# Microcontroller.net
KiCad netlist of a schematic drawn in Altium Designer
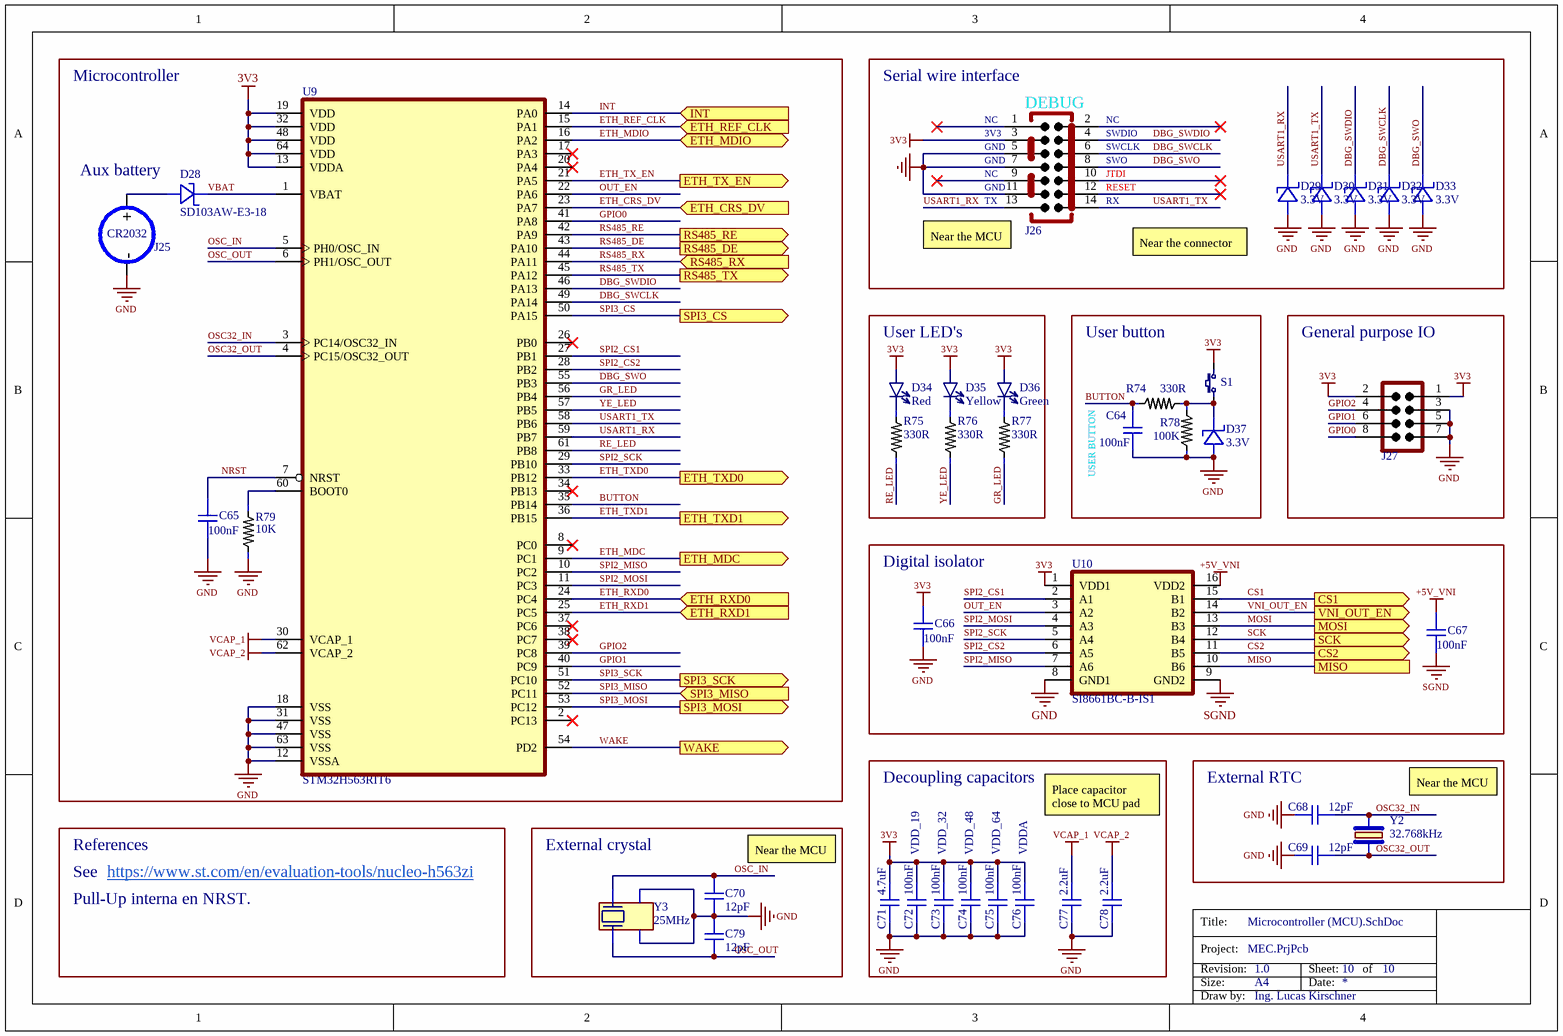
[diagram p0: Microcontroller (MCU).SchDoc]

(export (version "E")
  (design (tool "Eeschema 10.0.6"))
  (components
    (comp (ref "C64")
      (value "100nF")
      (footprint "CAPC1005N")
      (description "Multilayer Ceramic Capacitors MLCC - SMD/SMT 50 V 0.1uF X7R 0402 10%")
      (fields (field (name "PART NUMBER") "CC0402KRX5R9BB104") (field (name "MANUFACTURER") "YAGEO"))
      (libsource (lib "SchLib") (part "C-MLCC-100nF-50V-10%-0402"))
    )
    (comp (ref "C65")
      (value "100nF")
      (footprint "CAPC1005N")
      (description "Multilayer Ceramic Capacitors MLCC - SMD/SMT 50 V 0.1uF X7R 0402 10%")
      (fields (field (name "PART NUMBER") "CC0402KRX5R9BB104") (field (name "MANUFACTURER") "YAGEO"))
      (libsource (lib "SchLib") (part "C-MLCC-100nF-50V-10%-0402"))
    )
    (comp (ref "C66")
      (value "100nF")
      (footprint "CAPC1005N")
      (description "Multilayer Ceramic Capacitors MLCC - SMD/SMT 50 V 0.1uF X7R 0402 10%")
      (fields (field (name "PART NUMBER") "CC0402KRX5R9BB104") (field (name "MANUFACTURER") "YAGEO"))
      (libsource (lib "SchLib") (part "C-MLCC-100nF-50V-10%-0402"))
    )
    (comp (ref "C67")
      (value "100nF")
      (footprint "CAPC1005N")
      (description "Multilayer Ceramic Capacitors MLCC - SMD/SMT 50 V 0.1uF X7R 0402 10%")
      (fields (field (name "PART NUMBER") "CC0402KRX5R9BB104") (field (name "MANUFACTURER") "YAGEO"))
      (libsource (lib "SchLib") (part "C-MLCC-100nF-50V-10%-0402"))
    )
    (comp (ref "C68")
      (value "12pF")
      (footprint "CAPC1005N")
      (description "Multilayer Ceramic Capacitors MLCC - SMD/SMT 50 V 12 pF C0G 0402 1%")
      (fields (field (name "PART NUMBER") "CC0402FRNPO9BN120") (field (name "MANUFACTURER") "YAGEO"))
      (libsource (lib "SchLib") (part "C-MLCC-12pF-50V-10%-0402"))
    )
    (comp (ref "C69")
      (value "12pF")
      (footprint "CAPC1005N")
      (description "Multilayer Ceramic Capacitors MLCC - SMD/SMT 50 V 12 pF C0G 0402 1%")
      (fields (field (name "PART NUMBER") "CC0402FRNPO9BN120") (field (name "MANUFACTURER") "YAGEO"))
      (libsource (lib "SchLib") (part "C-MLCC-12pF-50V-10%-0402"))
    )
    (comp (ref "C70")
      (value "12pF")
      (footprint "CAPC1005N")
      (description "Multilayer Ceramic Capacitors MLCC - SMD/SMT 50 V 12 pF C0G 0402 1%")
      (fields (field (name "PART NUMBER") "CC0402FRNPO9BN120") (field (name "MANUFACTURER") "YAGEO"))
      (libsource (lib "SchLib") (part "C-MLCC-12pF-50V-10%-0402"))
    )
    (comp (ref "C71")
      (value "4.7uF")
      (footprint "CAPC1005N")
      (description "Multilayer Ceramic Capacitors MLCC - SMD/SMT 10V 4.7uF X5R 0402 10% HI CV")
      (fields (field (name "PART NUMBER") "CC0402KRX5R6BB475") (field (name "MANUFACTURER") "YAGEO"))
      (libsource (lib "SchLib") (part "C-MLCC-4.7uF-10V-10%-0402"))
    )
    (comp (ref "C72")
      (value "100nF")
      (footprint "CAPC1005N")
      (description "Multilayer Ceramic Capacitors MLCC - SMD/SMT 50 V 0.1uF X7R 0402 10%")
      (fields (field (name "PART NUMBER") "CC0402KRX5R9BB104") (field (name "MANUFACTURER") "YAGEO"))
      (libsource (lib "SchLib") (part "C-MLCC-100nF-50V-10%-0402"))
    )
    (comp (ref "C73")
      (value "100nF")
      (footprint "CAPC1005N")
      (description "Multilayer Ceramic Capacitors MLCC - SMD/SMT 50 V 0.1uF X7R 0402 10%")
      (fields (field (name "PART NUMBER") "CC0402KRX5R9BB104") (field (name "MANUFACTURER") "YAGEO"))
      (libsource (lib "SchLib") (part "C-MLCC-100nF-50V-10%-0402"))
    )
    (comp (ref "C74")
      (value "100nF")
      (footprint "CAPC1005N")
      (description "Multilayer Ceramic Capacitors MLCC - SMD/SMT 50 V 0.1uF X7R 0402 10%")
      (fields (field (name "PART NUMBER") "CC0402KRX5R9BB104") (field (name "MANUFACTURER") "YAGEO"))
      (libsource (lib "SchLib") (part "C-MLCC-100nF-50V-10%-0402"))
    )
    (comp (ref "C75")
      (value "100nF")
      (footprint "CAPC1005N")
      (description "Multilayer Ceramic Capacitors MLCC - SMD/SMT 50 V 0.1uF X7R 0402 10%")
      (fields (field (name "PART NUMBER") "CC0402KRX5R9BB104") (field (name "MANUFACTURER") "YAGEO"))
      (libsource (lib "SchLib") (part "C-MLCC-100nF-50V-10%-0402"))
    )
    (comp (ref "C76")
      (value "100nF")
      (footprint "CAPC1005N")
      (description "Multilayer Ceramic Capacitors MLCC - SMD/SMT 50 V 0.1uF X7R 0402 10%")
      (fields (field (name "PART NUMBER") "CC0402KRX5R9BB104") (field (name "MANUFACTURER") "YAGEO"))
      (libsource (lib "SchLib") (part "C-MLCC-100nF-50V-10%-0402"))
    )
    (comp (ref "C77")
      (value "2.2uF")
      (footprint "CAPC1005N")
      (description "Multilayer Ceramic Capacitors MLCC - SMD/SMT 25V 2.2uF X5R 0402 10% HI CV")
      (fields (field (name "PART NUMBER") "CC0402KRX5R8BB225") (field (name "MANUFACTURER") "YAGEO"))
      (libsource (lib "SchLib") (part "C-MLCC-2.2uF-25V-10%-0402"))
    )
    (comp (ref "C78")
      (value "2.2uF")
      (footprint "CAPC1005N")
      (description "Multilayer Ceramic Capacitors MLCC - SMD/SMT 25V 2.2uF X5R 0402 10% HI CV")
      (fields (field (name "PART NUMBER") "CC0402KRX5R8BB225") (field (name "MANUFACTURER") "YAGEO"))
      (libsource (lib "SchLib") (part "C-MLCC-2.2uF-25V-10%-0402"))
    )
    (comp (ref "C79")
      (value "12pF")
      (footprint "CAPC1005N")
      (description "Multilayer Ceramic Capacitors MLCC - SMD/SMT 50 V 12 pF C0G 0402 1%")
      (fields (field (name "PART NUMBER") "CC0402FRNPO9BN120") (field (name "MANUFACTURER") "YAGEO"))
      (libsource (lib "SchLib") (part "C-MLCC-12pF-50V-10%-0402"))
    )
    (comp (ref "D28")
      (value "Schottky Diodes")
      (footprint "SOD3705X110-2N")
      (description "Schottky Diodes & Rectifiers 350mA 40V SOD123")
      (fields
        (field (name "MANUFACTURER") "Vishay Semiconductors")
        (field (name "MOUSER PART #") "78-SD103AW-E3-18")
        (field (name "PART NUMBER") "SD103AW-E3-18")
      )
      (libsource (lib "SchLib") (part "D-SCH-350mA-40V-SOD123"))
    )
    (comp (ref "D29")
      (value "3.3V")
      (footprint "SOD2512X110N")
      (description "ESD Protection Diodes / TVS Diodes UNIDIRECTIONAL 3.3V ESD PR")
      (fields (field (name "MANUFACTURER") "onsemi") (field (name "PART NUMBER") "ESD7351HT1G"))
      (libsource (lib "SchLib") (part "D-TVS-36W-3.3V-SOD323"))
    )
    (comp (ref "D30")
      (value "3.3V")
      (footprint "SOD2512X110N")
      (description "ESD Protection Diodes / TVS Diodes UNIDIRECTIONAL 3.3V ESD PR")
      (fields (field (name "MANUFACTURER") "onsemi") (field (name "PART NUMBER") "ESD7351HT1G"))
      (libsource (lib "SchLib") (part "D-TVS-36W-3.3V-SOD323"))
    )
    (comp (ref "D31")
      (value "3.3V")
      (footprint "SOD2512X110N")
      (description "ESD Protection Diodes / TVS Diodes UNIDIRECTIONAL 3.3V ESD PR")
      (fields (field (name "MANUFACTURER") "onsemi") (field (name "PART NUMBER") "ESD7351HT1G"))
      (libsource (lib "SchLib") (part "D-TVS-36W-3.3V-SOD323"))
    )
    (comp (ref "D32")
      (value "3.3V")
      (footprint "SOD2512X110N")
      (description "ESD Protection Diodes / TVS Diodes UNIDIRECTIONAL 3.3V ESD PR")
      (fields (field (name "MANUFACTURER") "onsemi") (field (name "PART NUMBER") "ESD7351HT1G"))
      (libsource (lib "SchLib") (part "D-TVS-36W-3.3V-SOD323"))
    )
    (comp (ref "D33")
      (value "3.3V")
      (footprint "SOD2512X110N")
      (description "ESD Protection Diodes / TVS Diodes UNIDIRECTIONAL 3.3V ESD PR")
      (fields (field (name "MANUFACTURER") "onsemi") (field (name "PART NUMBER") "ESD7351HT1G"))
      (libsource (lib "SchLib") (part "D-TVS-36W-3.3V-SOD323"))
    )
    (comp (ref "D34")
      (value "Red")
      (footprint "LEDC1608X80N_RED")
      (description "Standard Single Color LEDs 0603 Red")
      (fields (field (name "PART NUMBER") "LTST-C190KRKT") (field (name "MANUFACTURER") "LITEON"))
      (libsource (lib "SchLib") (part "D-LED-RED-2V-20mA-0603"))
    )
    (comp (ref "D35")
      (value "Yellow")
      (footprint "LEDC1608X80N_YELLOW")
      (description "Standard Single Color LEDs 0603 Yellow")
      (fields (field (name "PART NUMBER") "LTST-C190KSKT") (field (name "MANUFACTURER") "LITEON"))
      (libsource (lib "SchLib") (part "D-LED-YELLOW-2V-20mA-0603"))
    )
    (comp (ref "D36")
      (value "Green")
      (footprint "LEDC1608X80N_GREEN")
      (description "Standard Single Color LEDs 0603 Green")
      (fields (field (name "PART NUMBER") "LTST-C190KGKT") (field (name "MANUFACTURER") "LITEON"))
      (libsource (lib "SchLib") (part "D-LED-GREEN-2V-20mA-0603"))
    )
    (comp (ref "D37")
      (value "3.3V")
      (footprint "SOD2512X110N")
      (description "ESD Protection Diodes / TVS Diodes UNIDIRECTIONAL 3.3V ESD PR")
      (fields (field (name "MANUFACTURER") "onsemi") (field (name "PART NUMBER") "ESD7351HT1G"))
      (libsource (lib "SchLib") (part "D-TVS-36W-3.3V-SOD323"))
    )
    (comp (ref "J25")
      (value "Cell Battery Holders")
      (footprint "CONB_BH_CR2032-2N")
      (description "Coin Cell Battery Holders CR2032")
      (fields (field (name "PART NUMBER") "1061") (field (name "MANUFACTURER") "Keystone Electronics"))
      (libsource (lib "SchLib") (part "J-CR2032-H-SMT"))
    )
    (comp (ref "J26")
      (value "Male straight header")
      (footprint "CONH_ML127P-14N")
      (description "Male straight header, 2 row, 14 positions, 1.27mm pitch, SMD")
      (fields (field (name "MANUFACTURER") "SAMTEC") (field (name "PART NUMBER") "FTSH-107-01-F-DV-K"))
      (libsource (lib "SchLib") (part "J-14-1P27-HDR-M-SH-SMT"))
    )
    (comp (ref "J27")
      (value "Male straight header")
      (footprint "CONH_ML254P-SMT-8N")
      (description "Male straight header, 2 row, 8 positions, 2.54mm pitch, SMD")
      (fields (field (name "PART NUMBER") "95278-101-08LF") (field (name "MANUFACTURER") "Amphenol FCI"))
      (libsource (lib "SchLib") (part "J-8-2P54-HDR-M-VERT-SMT"))
    )
    (comp (ref "R74")
      (value "330R")
      (footprint "RESC1005N")
      (description "Thick Film Resistors - SMD General Purpose Chip Resistor 0402, 330Ohms, 1%, 1/16W")
      (fields (field (name "PART NUMBER") "RC0402FR-07330RL") (field (name "MANUFACTURER") "YAGEO"))
      (libsource (lib "SchLib") (part "R-THICK-330R-62.5mW-1%-0402"))
    )
    (comp (ref "R75")
      (value "330R")
      (footprint "RESC1005N")
      (description "Thick Film Resistors - SMD General Purpose Chip Resistor 0402, 330Ohms, 1%, 1/16W")
      (fields (field (name "PART NUMBER") "RC0402FR-07330RL") (field (name "MANUFACTURER") "YAGEO"))
      (libsource (lib "SchLib") (part "R-THICK-330R-62.5mW-1%-0402"))
    )
    (comp (ref "R76")
      (value "330R")
      (footprint "RESC1005N")
      (description "Thick Film Resistors - SMD General Purpose Chip Resistor 0402, 330Ohms, 1%, 1/16W")
      (fields (field (name "PART NUMBER") "RC0402FR-07330RL") (field (name "MANUFACTURER") "YAGEO"))
      (libsource (lib "SchLib") (part "R-THICK-330R-62.5mW-1%-0402"))
    )
    (comp (ref "R77")
      (value "330R")
      (footprint "RESC1005N")
      (description "Thick Film Resistors - SMD General Purpose Chip Resistor 0402, 330Ohms, 1%, 1/16W")
      (fields (field (name "PART NUMBER") "RC0402FR-07330RL") (field (name "MANUFACTURER") "YAGEO"))
      (libsource (lib "SchLib") (part "R-THICK-330R-62.5mW-1%-0402"))
    )
    (comp (ref "R78")
      (value "100K")
      (footprint "RESC1005N")
      (description "Thick Film Resistors - SMD General Purpose Chip Resistor 0402, 100kOhms, 1%, 1/16W")
      (fields (field (name "PART NUMBER") "RC0402FR-07100KL") (field (name "MANUFACTURER") "YAGEO"))
      (libsource (lib "SchLib") (part "R-THICK-100K-62.5mW-1%-0402"))
    )
    (comp (ref "R79")
      (value "10K")
      (footprint "RESC1005N")
      (description "Thick Film Resistors - SMD General Purpose Chip Resistor 0402, 10kOhms, 1%, 1/16W")
      (fields (field (name "PART NUMBER") "RC0402FR-0710KL") (field (name "MANUFACTURER") "YAGEO"))
      (libsource (lib "SchLib") (part "R-THICK-10K-62.5mW-1%-0402"))
    )
    (comp (ref "S1")
      (value "Tactile Switches")
      (footprint "PKG3.5X6-2N")
      (description "Tactile Switches SMD OFF - (ON)")
      (fields (field (name "MANUFACTURER") "TE Connectivity") (field (name "PART NUMBER") "FSMSM"))
      (libsource (lib "SchLib") (part "S-TACT-NO-6x3.5-SMT"))
    )
    (comp (ref "U9")
      (value "ARM Cortex M33 MCU")
      (footprint "QFP50P1200X1200X160-64N")
      (fields
        (field (name "MANUFACTURER") "STMicroelectronics")
        (field (name "MOUSER PART #") "511-STM32H563RIT6")
        (field (name "DIGIKEY PART #") "497-STM32H563RIT6-ND")
        (field (name "PART NUMBER") "STM32H563RIT6")
      )
      (libsource (lib "SchLib") (part "U-STM32H563RI"))
    )
    (comp (ref "U10")
      (value "Digital Isolators")
      (footprint "SOIC127P1030X265-16N")
      (description "Digital Isolators 3.75 kV 5 forward & 1 reverse 6-channel isolator")
      (fields
        (field (name "MANUFACTURER") "Skyworks")
        (field (name "MOUSER PART #") "634-SI8661BC-B-IS1")
        (field (name "PART NUMBER") "SI8661BC-B-IS1")
      )
      (libsource (lib "SchLib") (part "U-SI8661BC-B-IS1"))
    )
    (comp (ref "Y2")
      (value "32.768kHz")
      (footprint "XTAL3215")
      (description "Crystals 32.768KHz 20ppm 12.5pF -40C +85C")
      (fields (field (name "PART NUMBER") "ECS-.327-12.5-34B-TR") (field (name "MANUFACTURER") "ECS"))
      (libsource (lib "SchLib") (part "Y-XTAL-32.768kHz-12pF-20ppm-3215-SMT"))
    )
    (comp (ref "Y3")
      (value "25MHz")
      (footprint "XTAL3225")
      (description "Crystals 25MHz 12pF 20ppm -40C +125C")
      (fields (field (name "MANUFACTURER") "ECS") (field (name "PART NUMBER") "ECS-250-12-33Q-JES-TR"))
      (libsource (lib "SchLib") (part "Y-XTAL-25MHz-12pF-20ppm-3225-SMT"))
    )
  )
  (nets
    (net (code "1") (name "+5V_VNI") (class "Default")
      (node (ref "C67") (pin "1") (pinfunction "1_1") (pintype "passive"))
      (node (ref "U10") (pin "16") (pinfunction "VDD2_16") (pintype "passive"))
    )
    (net (code "2") (name "/BUTTON") (class "Default")
      (node (ref "C64") (pin "1") (pinfunction "1_1") (pintype "passive"))
      (node (ref "R74") (pin "1") (pinfunction "1_1") (pintype "passive"))
      (node (ref "U9") (pin "35") (pinfunction "PB14_35") (pintype "passive"))
    )
    (net (code "3") (name "/CS1") (class "Default")
      (node (ref "U10") (pin "15") (pinfunction "B1_15") (pintype "passive"))
    )
    (net (code "4") (name "/CS2") (class "Default")
      (node (ref "U10") (pin "11") (pinfunction "B5_11") (pintype "passive"))
    )
    (net (code "5") (name "/DBG_SWCLK") (class "Default")
      (node (ref "D32") (pin "C") (pinfunction "C_C") (pintype "passive"))
      (node (ref "J26") (pin "6") (pinfunction "6_6") (pintype "passive"))
      (node (ref "U9") (pin "49") (pinfunction "PA14_49") (pintype "passive"))
    )
    (net (code "6") (name "/DBG_SWDIO") (class "Default")
      (node (ref "D31") (pin "C") (pinfunction "C_C") (pintype "passive"))
      (node (ref "J26") (pin "4") (pinfunction "4_4") (pintype "passive"))
      (node (ref "U9") (pin "46") (pinfunction "PA13_46") (pintype "passive"))
    )
    (net (code "7") (name "/DBG_SWO") (class "Default")
      (node (ref "D33") (pin "C") (pinfunction "C_C") (pintype "passive"))
      (node (ref "J26") (pin "8") (pinfunction "8_8") (pintype "passive"))
      (node (ref "U9") (pin "55") (pinfunction "PB3_55") (pintype "passive"))
    )
    (net (code "8") (name "/ETH_CRS_DV") (class "Default")
      (node (ref "U9") (pin "23") (pinfunction "PA7_23") (pintype "passive"))
    )
    (net (code "9") (name "/ETH_MDC") (class "Default")
      (node (ref "U9") (pin "9") (pinfunction "PC1_9") (pintype "passive"))
    )
    (net (code "10") (name "/ETH_MDIO") (class "Default")
      (node (ref "U9") (pin "16") (pinfunction "PA2_16") (pintype "passive"))
    )
    (net (code "11") (name "/ETH_REF_CLK") (class "Default")
      (node (ref "U9") (pin "15") (pinfunction "PA1_15") (pintype "passive"))
    )
    (net (code "12") (name "/ETH_RXD0") (class "Default")
      (node (ref "U9") (pin "24") (pinfunction "PC4_24") (pintype "passive"))
    )
    (net (code "13") (name "/ETH_RXD1") (class "Default")
      (node (ref "U9") (pin "25") (pinfunction "PC5_25") (pintype "passive"))
    )
    (net (code "14") (name "/ETH_TXD0") (class "Default")
      (node (ref "U9") (pin "33") (pinfunction "PB12_33") (pintype "passive"))
    )
    (net (code "15") (name "/ETH_TXD1") (class "Default")
      (node (ref "U9") (pin "36") (pinfunction "PB15_36") (pintype "passive"))
    )
    (net (code "16") (name "/ETH_TX_EN") (class "Default")
      (node (ref "U9") (pin "21") (pinfunction "PA5_21") (pintype "passive"))
    )
    (net (code "17") (name "/GPIO0") (class "Default")
      (node (ref "J27") (pin "8") (pinfunction "8_8") (pintype "passive"))
      (node (ref "U9") (pin "41") (pinfunction "PA8_41") (pintype "passive"))
    )
    (net (code "18") (name "/GPIO1") (class "Default")
      (node (ref "J27") (pin "6") (pinfunction "6_6") (pintype "passive"))
      (node (ref "U9") (pin "40") (pinfunction "PC9_40") (pintype "passive"))
    )
    (net (code "19") (name "/GPIO2") (class "Default")
      (node (ref "J27") (pin "4") (pinfunction "4_4") (pintype "passive"))
      (node (ref "U9") (pin "39") (pinfunction "PC8_39") (pintype "passive"))
    )
    (net (code "20") (name "/GR_LED") (class "Default")
      (node (ref "R77") (pin "1") (pinfunction "1_1") (pintype "passive"))
      (node (ref "U9") (pin "56") (pinfunction "PB4_56") (pintype "passive"))
    )
    (net (code "21") (name "/INT") (class "Default")
      (node (ref "U9") (pin "14") (pinfunction "PA0_14") (pintype "passive"))
    )
    (net (code "22") (name "/MISO") (class "Default")
      (node (ref "U10") (pin "10") (pinfunction "B6_10") (pintype "passive"))
    )
    (net (code "23") (name "/MOSI") (class "Default")
      (node (ref "U10") (pin "13") (pinfunction "B3_13") (pintype "passive"))
    )
    (net (code "24") (name "/NRST") (class "Default")
      (node (ref "C65") (pin "1") (pinfunction "1_1") (pintype "passive"))
      (node (ref "U9") (pin "7") (pinfunction "NRST_7") (pintype "passive"))
    )
    (net (code "25") (name "/OSC32_IN") (class "Default")
      (node (ref "C68") (pin "1") (pinfunction "1_1") (pintype "passive"))
      (node (ref "U9") (pin "3") (pinfunction "PC14/OSC32_IN_3") (pintype "passive"))
      (node (ref "Y2") (pin "2") (pinfunction "CRYSTAL_2") (pintype "passive"))
    )
    (net (code "26") (name "/OSC32_OUT") (class "Default")
      (node (ref "C69") (pin "1") (pinfunction "1_1") (pintype "passive"))
      (node (ref "U9") (pin "4") (pinfunction "PC15/OSC32_OUT_4") (pintype "passive"))
      (node (ref "Y2") (pin "1") (pinfunction "CRYSTAL_1") (pintype "passive"))
    )
    (net (code "27") (name "/OSC_IN") (class "Default")
      (node (ref "C70") (pin "1") (pinfunction "1_1") (pintype "passive"))
      (node (ref "U9") (pin "5") (pinfunction "PH0/OSC_IN_5") (pintype "passive"))
      (node (ref "Y3") (pin "1") (pinfunction "IN/OUT_1") (pintype "passive"))
    )
    (net (code "28") (name "/OSC_OUT") (class "Default")
      (node (ref "C79") (pin "2") (pinfunction "2_2") (pintype "passive"))
      (node (ref "U9") (pin "6") (pinfunction "PH1/OSC_OUT_6") (pintype "passive"))
      (node (ref "Y3") (pin "3") (pinfunction "OUT/IN_3") (pintype "passive"))
    )
    (net (code "29") (name "/OUT_EN") (class "Default")
      (node (ref "U10") (pin "3") (pinfunction "A2_3") (pintype "passive"))
      (node (ref "U9") (pin "22") (pinfunction "PA6_22") (pintype "passive"))
    )
    (net (code "30") (name "/RE_LED") (class "Default")
      (node (ref "R75") (pin "1") (pinfunction "1_1") (pintype "passive"))
      (node (ref "U9") (pin "61") (pinfunction "PB8_61") (pintype "passive"))
    )
    (net (code "31") (name "/RS485_DE") (class "Default")
      (node (ref "U9") (pin "43") (pinfunction "PA10_43") (pintype "passive"))
    )
    (net (code "32") (name "/RS485_RE") (class "Default")
      (node (ref "U9") (pin "42") (pinfunction "PA9_42") (pintype "passive"))
    )
    (net (code "33") (name "/RS485_RX") (class "Default")
      (node (ref "U9") (pin "44") (pinfunction "PA11_44") (pintype "passive"))
    )
    (net (code "34") (name "/RS485_TX") (class "Default")
      (node (ref "U9") (pin "45") (pinfunction "PA12_45") (pintype "passive"))
    )
    (net (code "35") (name "/SCK") (class "Default")
      (node (ref "U10") (pin "12") (pinfunction "B4_12") (pintype "passive"))
    )
    (net (code "36") (name "/SPI2_CS1") (class "Default")
      (node (ref "U10") (pin "2") (pinfunction "A1_2") (pintype "passive"))
      (node (ref "U9") (pin "27") (pinfunction "PB1_27") (pintype "passive"))
    )
    (net (code "37") (name "/SPI2_CS2") (class "Default")
      (node (ref "U10") (pin "6") (pinfunction "A5_6") (pintype "passive"))
      (node (ref "U9") (pin "28") (pinfunction "PB2_28") (pintype "passive"))
    )
    (net (code "38") (name "/SPI2_MISO") (class "Default")
      (node (ref "U10") (pin "7") (pinfunction "A6_7") (pintype "passive"))
      (node (ref "U9") (pin "10") (pinfunction "PC2_10") (pintype "passive"))
    )
    (net (code "39") (name "/SPI2_MOSI") (class "Default")
      (node (ref "U10") (pin "4") (pinfunction "A3_4") (pintype "passive"))
      (node (ref "U9") (pin "11") (pinfunction "PC3_11") (pintype "passive"))
    )
    (net (code "40") (name "/SPI2_SCK") (class "Default")
      (node (ref "U10") (pin "5") (pinfunction "A4_5") (pintype "passive"))
      (node (ref "U9") (pin "29") (pinfunction "PB10_29") (pintype "passive"))
    )
    (net (code "41") (name "/SPI3_CS") (class "Default")
      (node (ref "U9") (pin "50") (pinfunction "PA15_50") (pintype "passive"))
    )
    (net (code "42") (name "/SPI3_MISO") (class "Default")
      (node (ref "U9") (pin "52") (pinfunction "PC11_52") (pintype "passive"))
    )
    (net (code "43") (name "/SPI3_MOSI") (class "Default")
      (node (ref "U9") (pin "53") (pinfunction "PC12_53") (pintype "passive"))
    )
    (net (code "44") (name "/SPI3_SCK") (class "Default")
      (node (ref "U9") (pin "51") (pinfunction "PC10_51") (pintype "passive"))
    )
    (net (code "45") (name "/USART1_RX") (class "Default")
      (node (ref "D29") (pin "C") (pinfunction "C_C") (pintype "passive"))
      (node (ref "J26") (pin "13") (pinfunction "13_13") (pintype "passive"))
      (node (ref "U9") (pin "59") (pinfunction "PB7_59") (pintype "passive"))
    )
    (net (code "46") (name "/USART1_TX") (class "Default")
      (node (ref "D30") (pin "C") (pinfunction "C_C") (pintype "passive"))
      (node (ref "J26") (pin "14") (pinfunction "14_14") (pintype "passive"))
      (node (ref "U9") (pin "58") (pinfunction "PB6_58") (pintype "passive"))
    )
    (net (code "47") (name "/VBAT") (class "Default")
      (node (ref "D28") (pin "C") (pinfunction "C_C") (pintype "passive"))
      (node (ref "U9") (pin "1") (pinfunction "VBAT_1") (pintype "passive"))
    )
    (net (code "48") (name "/VNI_OUT_EN") (class "Default")
      (node (ref "U10") (pin "14") (pinfunction "B2_14") (pintype "passive"))
    )
    (net (code "49") (name "/WAKE") (class "Default")
      (node (ref "U9") (pin "54") (pinfunction "PD2_54") (pintype "passive"))
    )
    (net (code "50") (name "/YE_LED") (class "Default")
      (node (ref "R76") (pin "1") (pinfunction "1_1") (pintype "passive"))
      (node (ref "U9") (pin "57") (pinfunction "PB5_57") (pintype "passive"))
    )
    (net (code "51") (name "3V3") (class "Default")
      (node (ref "C66") (pin "1") (pinfunction "1_1") (pintype "passive"))
      (node (ref "C71") (pin "1") (pinfunction "1_1") (pintype "passive"))
      (node (ref "C72") (pin "1") (pinfunction "1_1") (pintype "passive"))
      (node (ref "C73") (pin "1") (pinfunction "1_1") (pintype "passive"))
      (node (ref "C74") (pin "1") (pinfunction "1_1") (pintype "passive"))
      (node (ref "C75") (pin "1") (pinfunction "1_1") (pintype "passive"))
      (node (ref "C76") (pin "1") (pinfunction "1_1") (pintype "passive"))
      (node (ref "D34") (pin "A") (pinfunction "A_A") (pintype "passive"))
      (node (ref "D35") (pin "A") (pinfunction "A_A") (pintype "passive"))
      (node (ref "D36") (pin "A") (pinfunction "A_A") (pintype "passive"))
      (node (ref "J26") (pin "3") (pinfunction "3_3") (pintype "passive"))
      (node (ref "J27") (pin "1") (pinfunction "1_1") (pintype "passive"))
      (node (ref "J27") (pin "2") (pinfunction "2_2") (pintype "passive"))
      (node (ref "S1") (pin "2") (pinfunction "2_2") (pintype "passive"))
      (node (ref "U10") (pin "1") (pinfunction "VDD1_1") (pintype "passive"))
      (node (ref "U9") (pin "13") (pinfunction "VDDA_13") (pintype "passive"))
      (node (ref "U9") (pin "19") (pinfunction "VDD_19") (pintype "passive"))
      (node (ref "U9") (pin "32") (pinfunction "VDD_32") (pintype "passive"))
      (node (ref "U9") (pin "48") (pinfunction "VDD_48") (pintype "passive"))
      (node (ref "U9") (pin "64") (pinfunction "VDD_64") (pintype "passive"))
    )
    (net (code "52") (name "GND") (class "Default")
      (node (ref "C64") (pin "2") (pinfunction "2_2") (pintype "passive"))
      (node (ref "C65") (pin "2") (pinfunction "2_2") (pintype "passive"))
      (node (ref "C66") (pin "2") (pinfunction "2_2") (pintype "passive"))
      (node (ref "C68") (pin "2") (pinfunction "2_2") (pintype "passive"))
      (node (ref "C69") (pin "2") (pinfunction "2_2") (pintype "passive"))
      (node (ref "C70") (pin "2") (pinfunction "2_2") (pintype "passive"))
      (node (ref "C71") (pin "2") (pinfunction "2_2") (pintype "passive"))
      (node (ref "C72") (pin "2") (pinfunction "2_2") (pintype "passive"))
      (node (ref "C73") (pin "2") (pinfunction "2_2") (pintype "passive"))
      (node (ref "C74") (pin "2") (pinfunction "2_2") (pintype "passive"))
      (node (ref "C75") (pin "2") (pinfunction "2_2") (pintype "passive"))
      (node (ref "C76") (pin "2") (pinfunction "2_2") (pintype "passive"))
      (node (ref "C77") (pin "2") (pinfunction "2_2") (pintype "passive"))
      (node (ref "C78") (pin "2") (pinfunction "2_2") (pintype "passive"))
      (node (ref "C79") (pin "1") (pinfunction "1_1") (pintype "passive"))
      (node (ref "D29") (pin "A") (pinfunction "A_A") (pintype "passive"))
      (node (ref "D30") (pin "A") (pinfunction "A_A") (pintype "passive"))
      (node (ref "D31") (pin "A") (pinfunction "A_A") (pintype "passive"))
      (node (ref "D32") (pin "A") (pinfunction "A_A") (pintype "passive"))
      (node (ref "D33") (pin "A") (pinfunction "A_A") (pintype "passive"))
      (node (ref "D37") (pin "A") (pinfunction "A_A") (pintype "passive"))
      (node (ref "J25") (pin "1") (pinfunction "-_1") (pintype "passive"))
      (node (ref "J26") (pin "11") (pinfunction "11_11") (pintype "passive"))
      (node (ref "J26") (pin "5") (pinfunction "5_5") (pintype "passive"))
      (node (ref "J26") (pin "7") (pinfunction "7_7") (pintype "passive"))
      (node (ref "J27") (pin "3") (pinfunction "3_3") (pintype "passive"))
      (node (ref "J27") (pin "5") (pinfunction "5_5") (pintype "passive"))
      (node (ref "J27") (pin "7") (pinfunction "7_7") (pintype "passive"))
      (node (ref "R78") (pin "1") (pinfunction "1_1") (pintype "passive"))
      (node (ref "R79") (pin "1") (pinfunction "1_1") (pintype "passive"))
      (node (ref "U10") (pin "8") (pinfunction "GND1_8") (pintype "passive"))
      (node (ref "U9") (pin "12") (pinfunction "VSSA_12") (pintype "passive"))
      (node (ref "U9") (pin "18") (pinfunction "VSS_18") (pintype "passive"))
      (node (ref "U9") (pin "31") (pinfunction "VSS_31") (pintype "passive"))
      (node (ref "U9") (pin "47") (pinfunction "VSS_47") (pintype "passive"))
      (node (ref "U9") (pin "63") (pinfunction "VSS_63") (pintype "passive"))
      (node (ref "Y3") (pin "2") (pinfunction "GND_2") (pintype "passive"))
      (node (ref "Y3") (pin "4") (pinfunction "GND_4") (pintype "passive"))
    )
    (net (code "53") (name "Net-(D34-PadC)") (class "Default")
      (node (ref "D34") (pin "C") (pinfunction "C_C") (pintype "passive"))
      (node (ref "R75") (pin "2") (pinfunction "2_2") (pintype "passive"))
    )
    (net (code "54") (name "Net-(D35-PadC)") (class "Default")
      (node (ref "D35") (pin "C") (pinfunction "C_C") (pintype "passive"))
      (node (ref "R76") (pin "2") (pinfunction "2_2") (pintype "passive"))
    )
    (net (code "55") (name "Net-(D36-PadC)") (class "Default")
      (node (ref "D36") (pin "C") (pinfunction "C_C") (pintype "passive"))
      (node (ref "R77") (pin "2") (pinfunction "2_2") (pintype "passive"))
    )
    (net (code "56") (name "Net-(D37-PadC)") (class "Default")
      (node (ref "D37") (pin "C") (pinfunction "C_C") (pintype "passive"))
      (node (ref "R74") (pin "2") (pinfunction "2_2") (pintype "passive"))
      (node (ref "R78") (pin "2") (pinfunction "2_2") (pintype "passive"))
      (node (ref "S1") (pin "1") (pinfunction "1_1") (pintype "passive"))
    )
    (net (code "57") (name "Net-(J25-+)") (class "Default")
      (node (ref "D28") (pin "A") (pinfunction "A_A") (pintype "passive"))
      (node (ref "J25") (pin "2") (pinfunction "+_2") (pintype "passive"))
    )
    (net (code "58") (name "Net-(U9-BOOT0)") (class "Default")
      (node (ref "R79") (pin "2") (pinfunction "2_2") (pintype "passive"))
      (node (ref "U9") (pin "60") (pinfunction "BOOT0_60") (pintype "passive"))
    )
    (net (code "59") (name "SGND") (class "Default")
      (node (ref "C67") (pin "2") (pinfunction "2_2") (pintype "passive"))
      (node (ref "U10") (pin "9") (pinfunction "GND2_9") (pintype "passive"))
    )
    (net (code "60") (name "VCAP_1") (class "Default")
      (node (ref "C77") (pin "1") (pinfunction "1_1") (pintype "passive"))
      (node (ref "U9") (pin "30") (pinfunction "VCAP_1_30") (pintype "passive"))
    )
    (net (code "61") (name "VCAP_2") (class "Default")
      (node (ref "C78") (pin "1") (pinfunction "1_1") (pintype "passive"))
      (node (ref "U9") (pin "62") (pinfunction "VCAP_2_62") (pintype "passive"))
    )
    (net (code "62") (name "unconnected-(J26-Pad1)") (class "Default")
      (node (ref "J26") (pin "1") (pinfunction "1_1") (pintype "passive+no_connect"))
    )
    (net (code "63") (name "unconnected-(J26-Pad2)") (class "Default")
      (node (ref "J26") (pin "2") (pinfunction "2_2") (pintype "passive+no_connect"))
    )
    (net (code "64") (name "unconnected-(J26-Pad9)") (class "Default")
      (node (ref "J26") (pin "9") (pinfunction "9_9") (pintype "passive+no_connect"))
    )
    (net (code "65") (name "unconnected-(J26-Pad10)") (class "Default")
      (node (ref "J26") (pin "10") (pinfunction "10_10") (pintype "passive+no_connect"))
    )
    (net (code "66") (name "unconnected-(J26-Pad12)") (class "Default")
      (node (ref "J26") (pin "12") (pinfunction "12_12") (pintype "passive+no_connect"))
    )
    (net (code "67") (name "unconnected-(U9-PA3-Pad17)") (class "Default")
      (node (ref "U9") (pin "17") (pinfunction "PA3_17") (pintype "passive+no_connect"))
    )
    (net (code "68") (name "unconnected-(U9-PA4-Pad20)") (class "Default")
      (node (ref "U9") (pin "20") (pinfunction "PA4_20") (pintype "passive+no_connect"))
    )
    (net (code "69") (name "unconnected-(U9-PB0-Pad26)") (class "Default")
      (node (ref "U9") (pin "26") (pinfunction "PB0_26") (pintype "passive+no_connect"))
    )
    (net (code "70") (name "unconnected-(U9-PB13-Pad34)") (class "Default")
      (node (ref "U9") (pin "34") (pinfunction "PB13_34") (pintype "passive+no_connect"))
    )
    (net (code "71") (name "unconnected-(U9-PC0-Pad8)") (class "Default")
      (node (ref "U9") (pin "8") (pinfunction "PC0_8") (pintype "passive+no_connect"))
    )
    (net (code "72") (name "unconnected-(U9-PC6-Pad37)") (class "Default")
      (node (ref "U9") (pin "37") (pinfunction "PC6_37") (pintype "passive+no_connect"))
    )
    (net (code "73") (name "unconnected-(U9-PC7-Pad38)") (class "Default")
      (node (ref "U9") (pin "38") (pinfunction "PC7_38") (pintype "passive+no_connect"))
    )
    (net (code "74") (name "unconnected-(U9-PC13-Pad2)") (class "Default")
      (node (ref "U9") (pin "2") (pinfunction "PC13_2") (pintype "passive+no_connect"))
    )
  )
)
